# BUCKCONVERTER-MCU.net
KiCad netlist of a schematic drawn in Altium Designer
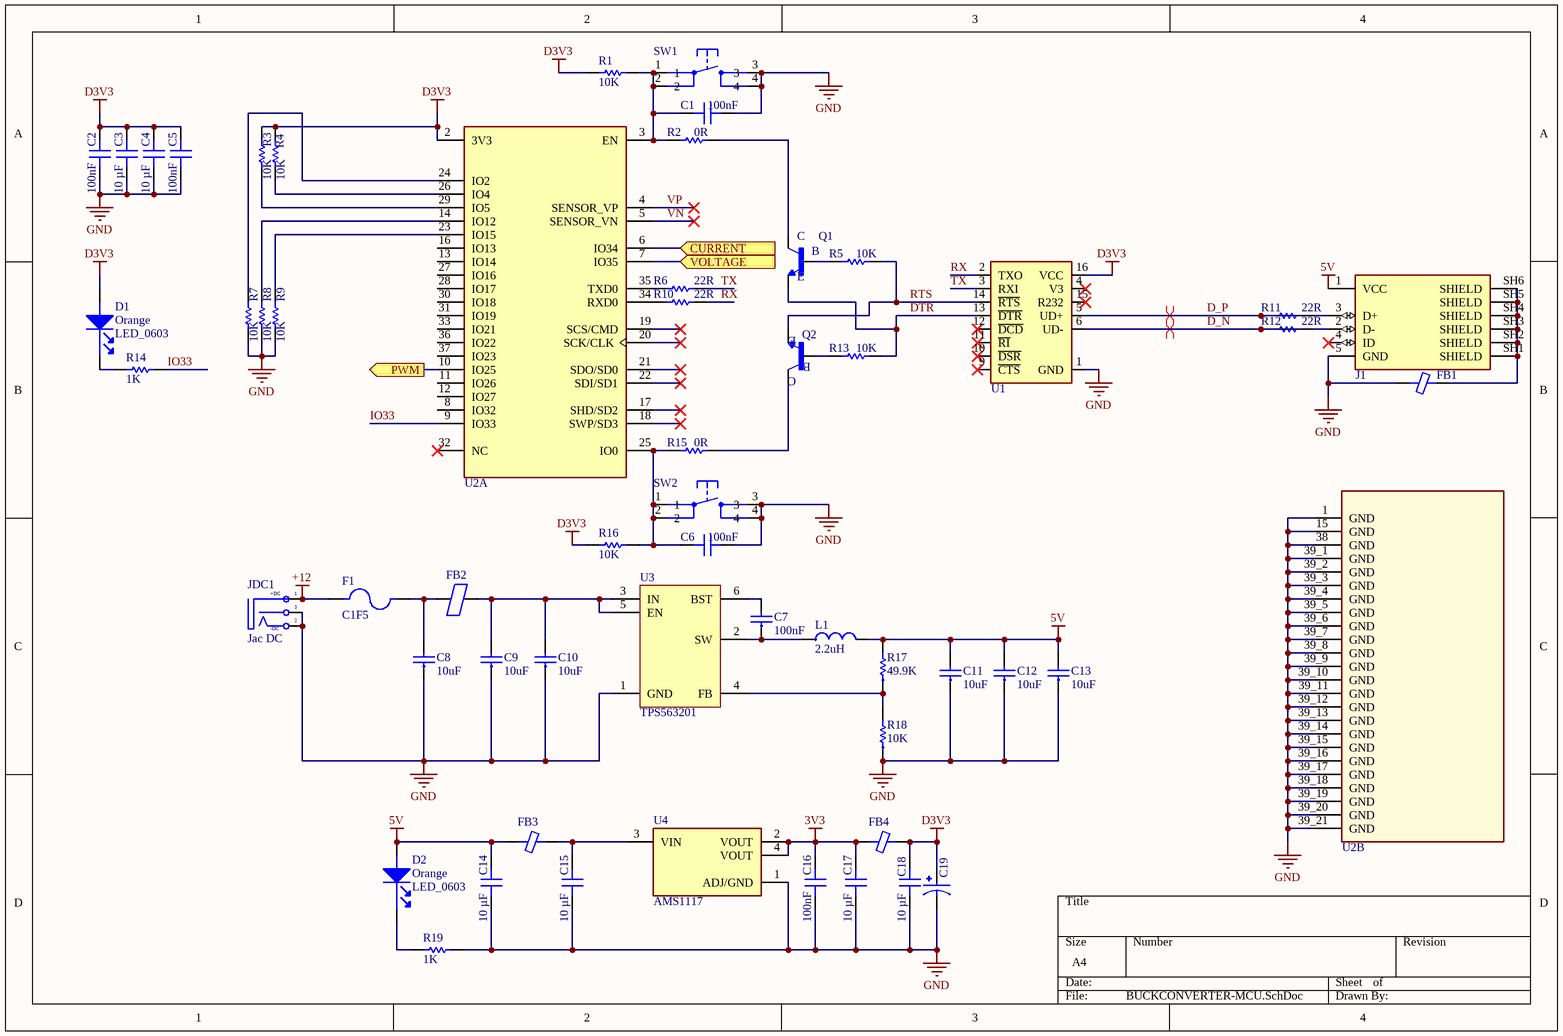
[diagram p0: BUCKCONVERTER-MCU.SchDoc]

(export (version "E")
  (design (tool "Eeschema 10.0.6"))
  (components
    (comp (ref "C1")
      (value "100nF")
      (footprint "CAP 0603")
      (description "CAP0603 X7R 10UF 10% 10V")
      (fields
        (field (name "PART NUMBER") "GMC10X7R106K10NT")
        (field (name "MANUFACTURER") "Cal-Chip Electronics, Inc.")
      )
      (libsource (lib "Celestial Altium Library - altium_library") (part "Capacitor"))
    )
    (comp (ref "C2")
      (value "100nF")
      (footprint "CAP 0603")
      (description "CAP0603 X7R 10UF 10% 10V")
      (fields
        (field (name "PART NUMBER") "GMC10X7R106K10NT")
        (field (name "MANUFACTURER") "Cal-Chip Electronics, Inc.")
      )
      (libsource (lib "Celestial Altium Library - altium_library") (part "Capacitor"))
    )
    (comp (ref "C3")
      (value "10 µF")
      (footprint "CAP 0603")
      (description "CAP0603 X7R 10UF 10% 10V")
      (fields
        (field (name "PART NUMBER") "GMC10X7R106K10NT")
        (field (name "MANUFACTURER") "Cal-Chip Electronics, Inc.")
      )
      (libsource (lib "Celestial Altium Library - altium_library") (part "Capacitor"))
    )
    (comp (ref "C4")
      (value "10 µF")
      (footprint "CAP 0603")
      (description "CAP0603 X7R 10UF 10% 10V")
      (fields
        (field (name "PART NUMBER") "GMC10X7R106K10NT")
        (field (name "MANUFACTURER") "Cal-Chip Electronics, Inc.")
      )
      (libsource (lib "Celestial Altium Library - altium_library") (part "Capacitor"))
    )
    (comp (ref "C5")
      (value "100nF")
      (footprint "CAP 0603")
      (description "CAP0603 X7R 10UF 10% 10V")
      (fields
        (field (name "PART NUMBER") "GMC10X7R106K10NT")
        (field (name "MANUFACTURER") "Cal-Chip Electronics, Inc.")
      )
      (libsource (lib "Celestial Altium Library - altium_library") (part "Capacitor"))
    )
    (comp (ref "C6")
      (value "100nF")
      (footprint "CAP 0603")
      (description "CAP0603 X7R 10UF 10% 10V")
      (fields
        (field (name "PART NUMBER") "GMC10X7R106K10NT")
        (field (name "MANUFACTURER") "Cal-Chip Electronics, Inc.")
      )
      (libsource (lib "Celestial Altium Library - altium_library") (part "Capacitor"))
    )
    (comp (ref "C7")
      (value "100nF")
      (footprint "CAP-CER0603-0.8H")
      (description "CAP CER 100nF 10% 50V X7R 0603 SMD")
      (libsource (lib "2502-GMQLITE-MAIN") (part "CAPCER0001 100nF 10% 50V X7R 0603 SMD_1"))
    )
    (comp (ref "C8")
      (value "10uF")
      (footprint "CAP-CER0402-20mil")
      (description "CAP CER 10uF 20% 6.3V X5R 0402 SMD")
      (libsource (lib "2502-GMQLITE-MAIN") (part "CAPCER0040 10uF 20% 6.3V X5R 0402 SMD"))
    )
    (comp (ref "C9")
      (value "10uF")
      (footprint "CAP-CER0402-20mil")
      (description "CAP CER 10uF 20% 6.3V X5R 0402 SMD")
      (libsource (lib "2502-GMQLITE-MAIN") (part "CAPCER0040 10uF 20% 6.3V X5R 0402 SMD"))
    )
    (comp (ref "C10")
      (value "10uF")
      (footprint "CAP-CER0402-20mil")
      (description "CAP CER 10uF 20% 6.3V X5R 0402 SMD")
      (libsource (lib "2502-GMQLITE-MAIN") (part "CAPCER0040 10uF 20% 6.3V X5R 0402 SMD"))
    )
    (comp (ref "C11")
      (value "10uF")
      (footprint "CAP-CER0402-20mil")
      (description "CAP CER 10uF 20% 6.3V X5R 0402 SMD")
      (libsource (lib "2502-GMQLITE-MAIN") (part "CAPCER0040 10uF 20% 6.3V X5R 0402 SMD"))
    )
    (comp (ref "C12")
      (value "10uF")
      (footprint "CAP-CER0402-20mil")
      (description "CAP CER 10uF 20% 6.3V X5R 0402 SMD")
      (libsource (lib "2502-GMQLITE-MAIN") (part "CAPCER0040 10uF 20% 6.3V X5R 0402 SMD"))
    )
    (comp (ref "C13")
      (value "10uF")
      (footprint "CAP-CER0402-20mil")
      (description "CAP CER 10uF 20% 6.3V X5R 0402 SMD")
      (libsource (lib "2502-GMQLITE-MAIN") (part "CAPCER0040 10uF 20% 6.3V X5R 0402 SMD"))
    )
    (comp (ref "C14")
      (value "10 µF")
      (footprint "CAP 0603")
      (description "CAP0603 X7R 10UF 10% 10V")
      (fields
        (field (name "PART NUMBER") "GMC10X7R106K10NT")
        (field (name "MANUFACTURER") "Cal-Chip Electronics, Inc.")
      )
      (libsource (lib "Celestial Altium Library - altium_library") (part "Capacitor"))
    )
    (comp (ref "C15")
      (value "10 µF")
      (footprint "CAP 0603")
      (description "CAP0603 X7R 10UF 10% 10V")
      (fields
        (field (name "PART NUMBER") "GMC10X7R106K10NT")
        (field (name "MANUFACTURER") "Cal-Chip Electronics, Inc.")
      )
      (libsource (lib "Celestial Altium Library - altium_library") (part "Capacitor"))
    )
    (comp (ref "C16")
      (value "100nF")
      (footprint "CAP 0603")
      (description "CAP0603 X7R 10UF 10% 10V")
      (fields
        (field (name "PART NUMBER") "GMC10X7R106K10NT")
        (field (name "MANUFACTURER") "Cal-Chip Electronics, Inc.")
      )
      (libsource (lib "Celestial Altium Library - altium_library") (part "Capacitor"))
    )
    (comp (ref "C17")
      (value "10 µF")
      (footprint "CAP 0603")
      (description "CAP0603 X7R 10UF 10% 10V")
      (fields
        (field (name "PART NUMBER") "GMC10X7R106K10NT")
        (field (name "MANUFACTURER") "Cal-Chip Electronics, Inc.")
      )
      (libsource (lib "Celestial Altium Library - altium_library") (part "Capacitor"))
    )
    (comp (ref "C18")
      (value "10 µF")
      (footprint "CAP 0603")
      (description "CAP0603 X7R 10UF 10% 10V")
      (fields
        (field (name "PART NUMBER") "GMC10X7R106K10NT")
        (field (name "MANUFACTURER") "Cal-Chip Electronics, Inc.")
      )
      (libsource (lib "Celestial Altium Library - altium_library") (part "Capacitor"))
    )
    (comp (ref "C19")
      (value "ECA1CHG331")
      (footprint "330UF-5mm")
      (fields (field (name "MP") "ECA-1CHG331") (field (name "MF") "Panasonic"))
      (libsource (lib "ECA1CHG331") (part "ECA1CHG331"))
    )
    (comp (ref "D1")
      (value "Orange")
      (footprint "LED")
      (description "LED SMARTLED ORANGE 606NM 0603")
      (fields
        (field (name "MANUFACTURER") "OSRAM Opto Semiconductors Inc")
        (field (name "MANUFACTURER PART NUMBER") "LO L29K-H2K1-24-Z")
        (field (name "PACKAGE / CASE") "LED_0603")
        (field (name "BY") "Hieu.Nguyen_20191030")
      )
      (libsource (lib "Stm32_Flyback_Driver_250814_1") (part "LED ORANGE 606NM 0603"))
    )
    (comp (ref "D2")
      (value "Orange")
      (footprint "LED")
      (description "LED SMARTLED ORANGE 606NM 0603")
      (fields
        (field (name "MANUFACTURER") "OSRAM Opto Semiconductors Inc")
        (field (name "MANUFACTURER PART NUMBER") "LO L29K-H2K1-24-Z")
        (field (name "PACKAGE / CASE") "LED_0603")
        (field (name "BY") "Hieu.Nguyen_20191030")
      )
      (libsource (lib "Stm32_Flyback_Driver_250814_1") (part "LED ORANGE 606NM 0603"))
    )
    (comp (ref "F1")
      (value "C1F5")
      (footprint "FUSE C1F5")
      (description "Fuse Chip Fast Acting 5A 125V SMD Solder Pad 1206 3.2 X 1.58 X 0.63mm")
      (fields (field (name "MANUFACTURER") "Bel TRP"))
      (libsource (lib "POWER_PIN_CAMERA") (part "C1F5"))
    )
    (comp (ref "FB1")
      (value "330 Ohms @ 100 MHz")
      (footprint "FB_0603")
      (description "FERRITE BEAD 330 OHM 0603 1LN")
      (fields
        (field (name "PART NUMBER") "BLM18KG331SH1D")
        (field (name "MANUFACTURER") "Murata Electronics")
      )
      (libsource (lib "Celestial Altium Library - altium_library") (part "Ferrite Chip"))
    )
    (comp (ref "FB2")
      (value "100MHz 2A 50mOhm")
      (footprint "FB 0603")
      (description "Ferrite Beads Multi-Layer 120Ohm 25% 100MHz 2A 50mOhm DCR 0603 Paper T/R")
      (fields
        (field (name "MANUFACTURER") "Murata")
        (field (name "MANUFACTURER PART NUMBER") "BLM18PG121SN1D")
      )
      (libsource (lib "POWER_PIN_CAMERA") (part "BLM18PG121SN1D"))
    )
    (comp (ref "FB3")
      (value "330 Ohms @ 100 MHz")
      (footprint "FB_0603")
      (description "FERRITE BEAD 330 OHM 0603 1LN")
      (fields
        (field (name "PART NUMBER") "BLM18KG331SH1D")
        (field (name "MANUFACTURER") "Murata Electronics")
      )
      (libsource (lib "Celestial Altium Library - altium_library") (part "Ferrite Chip"))
    )
    (comp (ref "FB4")
      (value "330 Ohms @ 100 MHz")
      (footprint "FB_0603")
      (description "FERRITE BEAD 330 OHM 0603 1LN")
      (fields
        (field (name "PART NUMBER") "BLM18KG331SH1D")
        (field (name "MANUFACTURER") "Murata Electronics")
      )
      (libsource (lib "Celestial Altium Library - altium_library") (part "Ferrite Chip"))
    )
    (comp (ref "J1")
      (value "MICRO B")
      (footprint "MICRO USB B")
      (libsource (lib "ESP32-S") (part "MICRO USB B"))
    )
    (comp (ref "JDC1")
      (value "Jac DC")
      (footprint "DC0")
      (description "Jac DC input")
      (libsource (lib "2502-GMQLITE-MAIN") (part "DCIN"))
    )
    (comp (ref "L1")
      (value "2.2uH")
      (footprint "IND-0420-2R2")
      (description "IND MOI 1W2T 2.2uH 20% 5A 0420 SMD")
      (libsource (lib "2502-GMQLITE-MAIN") (part "INDMOI0016 1W2T 2.2uH 20% 5A 0420 SMD"))
    )
    (comp (ref "Q1")
      (value "NMOS")
      (footprint "SOT23-3")
      (description "MMBT3904 Series 40 V CE Breakdown 0.2 A NPN General Purpose Amplifier - SOT-23")
      (fields (field (name "MANUFACTURER") "onsemi") (field (name "MANUFACTURER PART NUMBER") "MMBT3904"))
      (libsource (lib "Stm32_Flyback_Driver_250814_1") (part "MMBT3904"))
    )
    (comp (ref "Q2")
      (value "NMOS")
      (footprint "SOT23-3")
      (description "MMBT3904 Series 40 V CE Breakdown 0.2 A NPN General Purpose Amplifier - SOT-23")
      (fields (field (name "MANUFACTURER") "onsemi") (field (name "MANUFACTURER PART NUMBER") "MMBT3904"))
      (libsource (lib "") (part "MMBT3904_1"))
    )
    (comp (ref "R1")
      (value "10K")
      (footprint "Res 0603")
      (description "Res Thick Film 0603 2.2K Ohm 5% 1/10W ±200ppm/°C Molded SMD SMD Paper T/R")
      (fields
        (field (name "MANUFACTURER") "Vishay")
        (field (name "MANUFACTURER PART NUMBER") "CRCW06032K20JNEA")
      )
      (libsource (lib "Stm32_Flyback_Driver_250814_1") (part "Resistor 2.2K"))
    )
    (comp (ref "R2")
      (value "0R")
      (footprint "Res 0603")
      (description "Res Thick Film 0603 2.2K Ohm 5% 1/10W ±200ppm/°C Molded SMD SMD Paper T/R")
      (fields
        (field (name "MANUFACTURER") "Vishay")
        (field (name "MANUFACTURER PART NUMBER") "CRCW06032K20JNEA")
      )
      (libsource (lib "Stm32_Flyback_Driver_250814_1") (part "Resistor 2.2K"))
    )
    (comp (ref "R3")
      (value "10K")
      (footprint "Res 0603")
      (description "Res Thick Film 0603 2.2K Ohm 5% 1/10W ±200ppm/°C Molded SMD SMD Paper T/R")
      (fields
        (field (name "MANUFACTURER") "Vishay")
        (field (name "MANUFACTURER PART NUMBER") "CRCW06032K20JNEA")
      )
      (libsource (lib "Stm32_Flyback_Driver_250814_1") (part "Resistor 2.2K"))
    )
    (comp (ref "R4")
      (value "10K")
      (footprint "Res 0603")
      (description "Res Thick Film 0603 2.2K Ohm 5% 1/10W ±200ppm/°C Molded SMD SMD Paper T/R")
      (fields
        (field (name "MANUFACTURER") "Vishay")
        (field (name "MANUFACTURER PART NUMBER") "CRCW06032K20JNEA")
      )
      (libsource (lib "Stm32_Flyback_Driver_250814_1") (part "Resistor 2.2K"))
    )
    (comp (ref "R5")
      (value "10K")
      (footprint "Res 0603")
      (description "Res Thick Film 0603 2.2K Ohm 5% 1/10W ±200ppm/°C Molded SMD SMD Paper T/R")
      (fields
        (field (name "MANUFACTURER") "Vishay")
        (field (name "MANUFACTURER PART NUMBER") "CRCW06032K20JNEA")
      )
      (libsource (lib "Stm32_Flyback_Driver_250814_1") (part "Resistor 2.2K"))
    )
    (comp (ref "R6")
      (value "22R")
      (footprint "Res 0603")
      (description "Res Thick Film 0603 2.2K Ohm 5% 1/10W ±200ppm/°C Molded SMD SMD Paper T/R")
      (fields
        (field (name "MANUFACTURER") "Vishay")
        (field (name "MANUFACTURER PART NUMBER") "CRCW06032K20JNEA")
      )
      (libsource (lib "Stm32_Flyback_Driver_250814_1") (part "Resistor 2.2K"))
    )
    (comp (ref "R7")
      (value "10K")
      (footprint "Res 0603")
      (description "Res Thick Film 0603 2.2K Ohm 5% 1/10W ±200ppm/°C Molded SMD SMD Paper T/R")
      (fields
        (field (name "MANUFACTURER") "Vishay")
        (field (name "MANUFACTURER PART NUMBER") "CRCW06032K20JNEA")
      )
      (libsource (lib "Stm32_Flyback_Driver_250814_1") (part "Resistor 2.2K"))
    )
    (comp (ref "R8")
      (value "10K")
      (footprint "Res 0603")
      (description "Res Thick Film 0603 2.2K Ohm 5% 1/10W ±200ppm/°C Molded SMD SMD Paper T/R")
      (fields
        (field (name "MANUFACTURER") "Vishay")
        (field (name "MANUFACTURER PART NUMBER") "CRCW06032K20JNEA")
      )
      (libsource (lib "Stm32_Flyback_Driver_250814_1") (part "Resistor 2.2K"))
    )
    (comp (ref "R9")
      (value "10K")
      (footprint "Res 0603")
      (description "Res Thick Film 0603 2.2K Ohm 5% 1/10W ±200ppm/°C Molded SMD SMD Paper T/R")
      (fields
        (field (name "MANUFACTURER") "Vishay")
        (field (name "MANUFACTURER PART NUMBER") "CRCW06032K20JNEA")
      )
      (libsource (lib "Stm32_Flyback_Driver_250814_1") (part "Resistor 2.2K"))
    )
    (comp (ref "R10")
      (value "22R")
      (footprint "Res 0603")
      (description "Res Thick Film 0603 2.2K Ohm 5% 1/10W ±200ppm/°C Molded SMD SMD Paper T/R")
      (fields
        (field (name "MANUFACTURER") "Vishay")
        (field (name "MANUFACTURER PART NUMBER") "CRCW06032K20JNEA")
      )
      (libsource (lib "Stm32_Flyback_Driver_250814_1") (part "Resistor 2.2K"))
    )
    (comp (ref "R11")
      (value "22R")
      (footprint "Res 0603")
      (description "Res Thick Film 0603 2.2K Ohm 5% 1/10W ±200ppm/°C Molded SMD SMD Paper T/R")
      (fields
        (field (name "MANUFACTURER") "Vishay")
        (field (name "MANUFACTURER PART NUMBER") "CRCW06032K20JNEA")
      )
      (libsource (lib "Stm32_Flyback_Driver_250814_1") (part "Resistor 2.2K"))
    )
    (comp (ref "R12")
      (value "22R")
      (footprint "Res 0603")
      (description "Res Thick Film 0603 2.2K Ohm 5% 1/10W ±200ppm/°C Molded SMD SMD Paper T/R")
      (fields
        (field (name "MANUFACTURER") "Vishay")
        (field (name "MANUFACTURER PART NUMBER") "CRCW06032K20JNEA")
      )
      (libsource (lib "Stm32_Flyback_Driver_250814_1") (part "Resistor 2.2K"))
    )
    (comp (ref "R13")
      (value "10K")
      (footprint "Res 0603")
      (description "Res Thick Film 0603 2.2K Ohm 5% 1/10W ±200ppm/°C Molded SMD SMD Paper T/R")
      (fields
        (field (name "MANUFACTURER") "Vishay")
        (field (name "MANUFACTURER PART NUMBER") "CRCW06032K20JNEA")
      )
      (libsource (lib "Stm32_Flyback_Driver_250814_1") (part "Resistor 2.2K"))
    )
    (comp (ref "R14")
      (value "1K")
      (footprint "Res 0603")
      (description "Res Thick Film 0603 2.2K Ohm 5% 1/10W ±200ppm/°C Molded SMD SMD Paper T/R")
      (fields
        (field (name "MANUFACTURER") "Vishay")
        (field (name "MANUFACTURER PART NUMBER") "CRCW06032K20JNEA")
      )
      (libsource (lib "Stm32_Flyback_Driver_250814_1") (part "Resistor 2.2K"))
    )
    (comp (ref "R15")
      (value "0R")
      (footprint "Res 0603")
      (description "Res Thick Film 0603 2.2K Ohm 5% 1/10W ±200ppm/°C Molded SMD SMD Paper T/R")
      (fields
        (field (name "MANUFACTURER") "Vishay")
        (field (name "MANUFACTURER PART NUMBER") "CRCW06032K20JNEA")
      )
      (libsource (lib "Stm32_Flyback_Driver_250814_1") (part "Resistor 2.2K"))
    )
    (comp (ref "R16")
      (value "10K")
      (footprint "Res 0603")
      (description "Res Thick Film 0603 2.2K Ohm 5% 1/10W ±200ppm/°C Molded SMD SMD Paper T/R")
      (fields
        (field (name "MANUFACTURER") "Vishay")
        (field (name "MANUFACTURER PART NUMBER") "CRCW06032K20JNEA")
      )
      (libsource (lib "Stm32_Flyback_Driver_250814_1") (part "Resistor 2.2K"))
    )
    (comp (ref "R17")
      (value "49.9K")
      (footprint "RES-CHP0603-0.45H-272")
      (description "RES CHP 2K7 1% 1/10W 0603 SMD")
      (libsource (lib "2502-GMQLITE-MAIN") (part "RESCHP0195 2K7 1% 0603 SMD"))
    )
    (comp (ref "R18")
      (value "10K")
      (footprint "RES-CHP0603-0.45H-272")
      (description "RES CHP 2K7 1% 1/10W 0603 SMD")
      (libsource (lib "2502-GMQLITE-MAIN") (part "RESCHP0195 2K7 1% 0603 SMD"))
    )
    (comp (ref "R19")
      (value "1K")
      (footprint "Res 0603")
      (description "Res Thick Film 0603 2.2K Ohm 5% 1/10W ±200ppm/°C Molded SMD SMD Paper T/R")
      (fields
        (field (name "MANUFACTURER") "Vishay")
        (field (name "MANUFACTURER PART NUMBER") "CRCW06032K20JNEA")
      )
      (libsource (lib "Stm32_Flyback_Driver_250814_1") (part "Resistor 2.2K"))
    )
    (comp (ref "SW1")
      (value "SW2")
      (footprint "SWITCH")
      (description "Switch button 4 pin")
      (libsource (lib "Stm32_Flyback_Driver_250814_1") (part "SW2"))
    )
    (comp (ref "SW2")
      (value "SW2")
      (footprint "SWITCH")
      (description "Switch button 4 pin")
      (libsource (lib "Stm32_Flyback_Driver_250814_1") (part "SW2"))
    )
    (comp (ref "U1") (value "CH340C") (footprint "CH340C") (libsource (lib "ESP32-S") (part "CH340C")))
    (comp (ref "U2")
      (value "ESP32-WROOM-32UE-N8")
      (footprint "ESP32S")
      (description "Multiprotocol Modules SMD module ESP32-WROOM-32UE, ESP32-D0WD-V3, ESP32 ECO V3,")
      (fields (field (name "MANUFACTURER") "Espressif Systems"))
      (libsource (lib "ESP32-S") (part "ESP32-WROOM-32UE-N8"))
    )
    (comp (ref "U3")
      (value "TPS563201")
      (footprint "SOT23-6")
      (description "ICS OCV BCK TPS563201 3A SOT23-6 SMD")
      (libsource (lib "2502-GMQLITE-MAIN") (part "ICSOCV0021 BCK TPS563201 3A SOT23-6 SMD"))
    )
    (comp (ref "U4")
      (value "AMS1117")
      (footprint "AMS1117")
      (description "1A LOW DROPOUT VOLTAGE REGULATOR SOT-223")
      (fields (field (name "MF") "Advanced Monolithic Systems"))
      (libsource (lib "AMS1117") (part "AMS1117"))
    )
  )
  (nets
    (net (code "1") (name "+12") (class "Default")
      (node (ref "F1") (pin "1") (pinfunction "1_1") (pintype "passive"))
      (node (ref "JDC1") (pin "1") (pinfunction "T_1") (pintype "passive"))
    )
    (net (code "2") (name "/CURRENT") (class "Default")
      (node (ref "U2") (pin "6") (pinfunction "IO34_6") (pintype "passive"))
    )
    (net (code "3") (name "/DTR") (class "Default")
      (node (ref "Q1") (pin "2") (pinfunction "E_2") (pintype "passive"))
      (node (ref "R13") (pin "2") (pinfunction "2_2") (pintype "passive"))
      (node (ref "U1") (pin "13") (pinfunction "~{DTR}_13") (pintype "passive"))
    )
    (net (code "4") (name "/D_N") (class "Default")
      (node (ref "R12") (pin "1") (pinfunction "1_1") (pintype "passive"))
      (node (ref "U1") (pin "6") (pinfunction "UD-_6") (pintype "passive"))
    )
    (net (code "5") (name "/D_P") (class "Default")
      (node (ref "R11") (pin "1") (pinfunction "1_1") (pintype "passive"))
      (node (ref "U1") (pin "5") (pinfunction "UD+_5") (pintype "passive"))
    )
    (net (code "6") (name "/IO33") (class "Default")
      (node (ref "R14") (pin "2") (pinfunction "2_2") (pintype "passive"))
      (node (ref "U2") (pin "9") (pinfunction "IO33_9") (pintype "passive"))
    )
    (net (code "7") (name "/PWM") (class "Default")
      (node (ref "U2") (pin "10") (pinfunction "IO25_10") (pintype "passive"))
    )
    (net (code "8") (name "/RTS") (class "Default")
      (node (ref "Q2") (pin "2") (pinfunction "E_2") (pintype "passive"))
      (node (ref "R5") (pin "2") (pinfunction "2_2") (pintype "passive"))
      (node (ref "U1") (pin "14") (pinfunction "~{RTS}_14") (pintype "passive"))
    )
    (net (code "9") (name "/RX") (class "Default")
      (node (ref "R10") (pin "2") (pinfunction "2_2") (pintype "passive"))
      (node (ref "U1") (pin "2") (pinfunction "TXO_2") (pintype "passive"))
    )
    (net (code "10") (name "/TX") (class "Default")
      (node (ref "R6") (pin "2") (pinfunction "2_2") (pintype "passive"))
      (node (ref "U1") (pin "3") (pinfunction "RXI_3") (pintype "passive"))
    )
    (net (code "11") (name "/VN") (class "Default")
      (node (ref "U2") (pin "5") (pinfunction "SENSOR_VN_5") (pintype "passive+no_connect"))
    )
    (net (code "12") (name "/VOLTAGE") (class "Default")
      (node (ref "U2") (pin "7") (pinfunction "IO35_7") (pintype "passive"))
    )
    (net (code "13") (name "/VP") (class "Default")
      (node (ref "U2") (pin "4") (pinfunction "SENSOR_VP_4") (pintype "passive+no_connect"))
    )
    (net (code "14") (name "3V3") (class "Default")
      (node (ref "C16") (pin "2") (pinfunction "2_2") (pintype "passive"))
      (node (ref "C17") (pin "2") (pinfunction "2_2") (pintype "passive"))
      (node (ref "FB4") (pin "1") (pinfunction "1_1") (pintype "passive"))
      (node (ref "U4") (pin "2") (pinfunction "VOUT_2") (pintype "passive"))
      (node (ref "U4") (pin "4") (pinfunction "VOUT_4") (pintype "passive"))
    )
    (net (code "15") (name "5V") (class "Default")
      (node (ref "C11") (pin "2") (pinfunction "2_2") (pintype "passive"))
      (node (ref "C12") (pin "2") (pinfunction "2_2") (pintype "passive"))
      (node (ref "C13") (pin "2") (pinfunction "2_2") (pintype "passive"))
      (node (ref "C14") (pin "2") (pinfunction "2_2") (pintype "passive"))
      (node (ref "D2") (pin "1") (pinfunction "ANODE_1") (pintype "passive"))
      (node (ref "FB3") (pin "1") (pinfunction "1_1") (pintype "passive"))
      (node (ref "J1") (pin "1") (pinfunction "VCC_1") (pintype "power_in"))
      (node (ref "L1") (pin "2") (pinfunction "2_2") (pintype "passive"))
      (node (ref "R17") (pin "2") (pinfunction "2_2") (pintype "passive"))
    )
    (net (code "16") (name "D3V3") (class "Default")
      (node (ref "C18") (pin "2") (pinfunction "2_2") (pintype "passive"))
      (node (ref "C19") (pin "1") (pinfunction "1_1") (pintype "passive"))
      (node (ref "C2") (pin "2") (pinfunction "2_2") (pintype "passive"))
      (node (ref "C3") (pin "2") (pinfunction "2_2") (pintype "passive"))
      (node (ref "C4") (pin "2") (pinfunction "2_2") (pintype "passive"))
      (node (ref "C5") (pin "2") (pinfunction "2_2") (pintype "passive"))
      (node (ref "D1") (pin "1") (pinfunction "ANODE_1") (pintype "passive"))
      (node (ref "FB4") (pin "2") (pinfunction "2_2") (pintype "passive"))
      (node (ref "R1") (pin "1") (pinfunction "1_1") (pintype "passive"))
      (node (ref "R16") (pin "1") (pinfunction "1_1") (pintype "passive"))
      (node (ref "R3") (pin "2") (pinfunction "2_2") (pintype "passive"))
      (node (ref "R4") (pin "2") (pinfunction "2_2") (pintype "passive"))
      (node (ref "U1") (pin "16") (pinfunction "VCC_16") (pintype "passive"))
      (node (ref "U2") (pin "2") (pinfunction "3V3_2") (pintype "passive"))
    )
    (net (code "17") (name "GND") (class "Default")
      (node (ref "C1") (pin "1") (pinfunction "1_1") (pintype "passive"))
      (node (ref "C10") (pin "1") (pinfunction "1_1") (pintype "passive"))
      (node (ref "C11") (pin "1") (pinfunction "1_1") (pintype "passive"))
      (node (ref "C12") (pin "1") (pinfunction "1_1") (pintype "passive"))
      (node (ref "C13") (pin "1") (pinfunction "1_1") (pintype "passive"))
      (node (ref "C14") (pin "1") (pinfunction "1_1") (pintype "passive"))
      (node (ref "C15") (pin "1") (pinfunction "1_1") (pintype "passive"))
      (node (ref "C16") (pin "1") (pinfunction "1_1") (pintype "passive"))
      (node (ref "C17") (pin "1") (pinfunction "1_1") (pintype "passive"))
      (node (ref "C18") (pin "1") (pinfunction "1_1") (pintype "passive"))
      (node (ref "C19") (pin "2") (pinfunction "2_2") (pintype "passive"))
      (node (ref "C2") (pin "1") (pinfunction "1_1") (pintype "passive"))
      (node (ref "C3") (pin "1") (pinfunction "1_1") (pintype "passive"))
      (node (ref "C4") (pin "1") (pinfunction "1_1") (pintype "passive"))
      (node (ref "C5") (pin "1") (pinfunction "1_1") (pintype "passive"))
      (node (ref "C6") (pin "1") (pinfunction "1_1") (pintype "passive"))
      (node (ref "C8") (pin "1") (pinfunction "1_1") (pintype "passive"))
      (node (ref "C9") (pin "1") (pinfunction "1_1") (pintype "passive"))
      (node (ref "FB1") (pin "1") (pinfunction "1_1") (pintype "passive"))
      (node (ref "J1") (pin "5") (pinfunction "GND_5") (pintype "power_in"))
      (node (ref "JDC1") (pin "2") (pinfunction "TN_2") (pintype "passive"))
      (node (ref "JDC1") (pin "3") (pinfunction "S_3") (pintype "power_in"))
      (node (ref "R18") (pin "1") (pinfunction "1_1") (pintype "passive"))
      (node (ref "R19") (pin "2") (pinfunction "2_2") (pintype "passive"))
      (node (ref "R7") (pin "1") (pinfunction "1_1") (pintype "passive"))
      (node (ref "R8") (pin "1") (pinfunction "1_1") (pintype "passive"))
      (node (ref "R9") (pin "1") (pinfunction "1_1") (pintype "passive"))
      (node (ref "SW1") (pin "3") (pinfunction "3_3") (pintype "passive"))
      (node (ref "SW1") (pin "4") (pinfunction "4_4") (pintype "passive"))
      (node (ref "SW2") (pin "3") (pinfunction "3_3") (pintype "passive"))
      (node (ref "SW2") (pin "4") (pinfunction "4_4") (pintype "passive"))
      (node (ref "U1") (pin "1") (pinfunction "GND_1") (pintype "passive"))
      (node (ref "U2") (pin "1") (pinfunction "GND_1") (pintype "passive"))
      (node (ref "U2") (pin "15") (pinfunction "GND_15") (pintype "passive"))
      (node (ref "U2") (pin "38") (pinfunction "GND_38") (pintype "passive"))
      (node (ref "U2") (pin "39_1") (pinfunction "GND_39_1") (pintype "passive"))
      (node (ref "U2") (pin "39_10") (pinfunction "GND_39_10") (pintype "passive"))
      (node (ref "U2") (pin "39_11") (pinfunction "GND_39_11") (pintype "passive"))
      (node (ref "U2") (pin "39_12") (pinfunction "GND_39_12") (pintype "passive"))
      (node (ref "U2") (pin "39_13") (pinfunction "GND_39_13") (pintype "passive"))
      (node (ref "U2") (pin "39_14") (pinfunction "GND_39_14") (pintype "passive"))
      (node (ref "U2") (pin "39_15") (pinfunction "GND_39_15") (pintype "passive"))
      (node (ref "U2") (pin "39_16") (pinfunction "GND_39_16") (pintype "passive"))
      (node (ref "U2") (pin "39_17") (pinfunction "GND_39_17") (pintype "passive"))
      (node (ref "U2") (pin "39_18") (pinfunction "GND_39_18") (pintype "passive"))
      (node (ref "U2") (pin "39_19") (pinfunction "GND_39_19") (pintype "passive"))
      (node (ref "U2") (pin "39_2") (pinfunction "GND_39_2") (pintype "passive"))
      (node (ref "U2") (pin "39_20") (pinfunction "GND_39_20") (pintype "passive"))
      (node (ref "U2") (pin "39_21") (pinfunction "GND_39_21") (pintype "passive"))
      (node (ref "U2") (pin "39_3") (pinfunction "GND_39_3") (pintype "passive"))
      (node (ref "U2") (pin "39_4") (pinfunction "GND_39_4") (pintype "passive"))
      (node (ref "U2") (pin "39_5") (pinfunction "GND_39_5") (pintype "passive"))
      (node (ref "U2") (pin "39_6") (pinfunction "GND_39_6") (pintype "passive"))
      (node (ref "U2") (pin "39_7") (pinfunction "GND_39_7") (pintype "passive"))
      (node (ref "U2") (pin "39_8") (pinfunction "GND_39_8") (pintype "passive"))
      (node (ref "U2") (pin "39_9") (pinfunction "GND_39_9") (pintype "passive"))
      (node (ref "U3") (pin "1") (pinfunction "GND_1") (pintype "power_in"))
      (node (ref "U4") (pin "1") (pinfunction "ADJ/GND_1") (pintype "power_in"))
    )
    (net (code "18") (name "Net-(C8-Pad2)") (class "Default")
      (node (ref "C8") (pin "2") (pinfunction "2_2") (pintype "passive"))
      (node (ref "F1") (pin "2") (pinfunction "2_2") (pintype "passive"))
      (node (ref "FB2") (pin "1") (pinfunction "1_1") (pintype "passive"))
    )
    (net (code "19") (name "Net-(D1-cathode)") (class "Default")
      (node (ref "D1") (pin "2") (pinfunction "cathode_2") (pintype "passive"))
      (node (ref "R14") (pin "1") (pinfunction "1_1") (pintype "passive"))
    )
    (net (code "20") (name "Net-(D2-cathode)") (class "Default")
      (node (ref "D2") (pin "2") (pinfunction "cathode_2") (pintype "passive"))
      (node (ref "R19") (pin "1") (pinfunction "1_1") (pintype "passive"))
    )
    (net (code "21") (name "Net-(FB1-Pad2)") (class "Default")
      (node (ref "FB1") (pin "2") (pinfunction "2_2") (pintype "passive"))
      (node (ref "J1") (pin "SH1") (pinfunction "SHIELD_SH1") (pintype "passive"))
      (node (ref "J1") (pin "SH2") (pinfunction "SHIELD_SH2") (pintype "passive"))
      (node (ref "J1") (pin "SH3") (pinfunction "SHIELD_SH3") (pintype "passive"))
      (node (ref "J1") (pin "SH4") (pinfunction "SHIELD_SH4") (pintype "passive"))
      (node (ref "J1") (pin "SH5") (pinfunction "SHIELD_SH5") (pintype "passive"))
      (node (ref "J1") (pin "SH6") (pinfunction "SHIELD_SH6") (pintype "passive"))
    )
    (net (code "22") (name "Net-(J1-D+)") (class "Default")
      (node (ref "J1") (pin "3") (pinfunction "D+_3") (pintype "bidirectional"))
      (node (ref "R11") (pin "2") (pinfunction "2_2") (pintype "passive"))
    )
    (net (code "23") (name "Net-(J1-D-)") (class "Default")
      (node (ref "J1") (pin "2") (pinfunction "D-_2") (pintype "bidirectional"))
      (node (ref "R12") (pin "2") (pinfunction "2_2") (pintype "passive"))
    )
    (net (code "24") (name "Net-(Q1-B)") (class "Default")
      (node (ref "Q1") (pin "1") (pinfunction "B_1") (pintype "passive"))
      (node (ref "R5") (pin "1") (pinfunction "1_1") (pintype "passive"))
    )
    (net (code "25") (name "Net-(Q1-C)") (class "Default")
      (node (ref "Q1") (pin "3") (pinfunction "C_3") (pintype "passive"))
      (node (ref "R2") (pin "2") (pinfunction "2_2") (pintype "passive"))
    )
    (net (code "26") (name "Net-(Q2-B)") (class "Default")
      (node (ref "Q2") (pin "1") (pinfunction "B_1") (pintype "passive"))
      (node (ref "R13") (pin "1") (pinfunction "1_1") (pintype "passive"))
    )
    (net (code "27") (name "Net-(Q2-C)") (class "Default")
      (node (ref "Q2") (pin "3") (pinfunction "C_3") (pintype "passive"))
      (node (ref "R15") (pin "2") (pinfunction "2_2") (pintype "passive"))
    )
    (net (code "28") (name "Net-(U2A-EN)") (class "Default")
      (node (ref "C1") (pin "2") (pinfunction "2_2") (pintype "passive"))
      (node (ref "R1") (pin "2") (pinfunction "2_2") (pintype "passive"))
      (node (ref "R2") (pin "1") (pinfunction "1_1") (pintype "passive"))
      (node (ref "SW1") (pin "1") (pinfunction "1_1") (pintype "passive"))
      (node (ref "SW1") (pin "2") (pinfunction "2_2") (pintype "passive"))
      (node (ref "U2") (pin "3") (pinfunction "EN_3") (pintype "passive"))
    )
    (net (code "29") (name "Net-(U2A-IO0)") (class "Default")
      (node (ref "C6") (pin "2") (pinfunction "2_2") (pintype "passive"))
      (node (ref "R15") (pin "1") (pinfunction "1_1") (pintype "passive"))
      (node (ref "R16") (pin "2") (pinfunction "2_2") (pintype "passive"))
      (node (ref "SW2") (pin "1") (pinfunction "1_1") (pintype "passive"))
      (node (ref "SW2") (pin "2") (pinfunction "2_2") (pintype "passive"))
      (node (ref "U2") (pin "25") (pinfunction "IO0_25") (pintype "passive"))
    )
    (net (code "30") (name "Net-(U2A-IO2)") (class "Default")
      (node (ref "R7") (pin "2") (pinfunction "2_2") (pintype "passive"))
      (node (ref "U2") (pin "24") (pinfunction "IO2_24") (pintype "passive"))
    )
    (net (code "31") (name "Net-(U2A-IO4)") (class "Default")
      (node (ref "R4") (pin "1") (pinfunction "1_1") (pintype "passive"))
      (node (ref "U2") (pin "26") (pinfunction "IO4_26") (pintype "passive"))
    )
    (net (code "32") (name "Net-(U2A-IO5)") (class "Default")
      (node (ref "R3") (pin "1") (pinfunction "1_1") (pintype "passive"))
      (node (ref "U2") (pin "29") (pinfunction "IO5_29") (pintype "passive"))
    )
    (net (code "33") (name "Net-(U2A-IO12)") (class "Default")
      (node (ref "R8") (pin "2") (pinfunction "2_2") (pintype "passive"))
      (node (ref "U2") (pin "14") (pinfunction "IO12_14") (pintype "passive"))
    )
    (net (code "34") (name "Net-(U2A-IO15)") (class "Default")
      (node (ref "R9") (pin "2") (pinfunction "2_2") (pintype "passive"))
      (node (ref "U2") (pin "23") (pinfunction "IO15_23") (pintype "passive"))
    )
    (net (code "35") (name "Net-(U2A-RXD0)") (class "Default")
      (node (ref "R10") (pin "1") (pinfunction "1_1") (pintype "passive"))
      (node (ref "U2") (pin "34") (pinfunction "RXD0_34") (pintype "passive"))
    )
    (net (code "36") (name "Net-(U2A-TXD0)") (class "Default")
      (node (ref "R6") (pin "1") (pinfunction "1_1") (pintype "passive"))
      (node (ref "U2") (pin "35") (pinfunction "TXD0_35") (pintype "passive"))
    )
    (net (code "37") (name "Net-(U3-BST)") (class "Default")
      (node (ref "C7") (pin "2") (pinfunction "2_2") (pintype "passive"))
      (node (ref "U3") (pin "6") (pinfunction "BST_6") (pintype "passive"))
    )
    (net (code "38") (name "Net-(U3-EN)") (class "Default")
      (node (ref "C10") (pin "2") (pinfunction "2_2") (pintype "passive"))
      (node (ref "C9") (pin "2") (pinfunction "2_2") (pintype "passive"))
      (node (ref "FB2") (pin "2") (pinfunction "2_2") (pintype "passive"))
      (node (ref "U3") (pin "3") (pinfunction "IN_3") (pintype "power_in"))
      (node (ref "U3") (pin "5") (pinfunction "EN_5") (pintype "passive"))
    )
    (net (code "39") (name "Net-(U3-FB)") (class "Default")
      (node (ref "R17") (pin "1") (pinfunction "1_1") (pintype "passive"))
      (node (ref "R18") (pin "2") (pinfunction "2_2") (pintype "passive"))
      (node (ref "U3") (pin "4") (pinfunction "FB_4") (pintype "passive"))
    )
    (net (code "40") (name "Net-(U3-SW)") (class "Default")
      (node (ref "C7") (pin "1") (pinfunction "1_1") (pintype "passive"))
      (node (ref "L1") (pin "1") (pinfunction "1_1") (pintype "passive"))
      (node (ref "U3") (pin "2") (pinfunction "SW_2") (pintype "passive"))
    )
    (net (code "41") (name "Net-(U4-VIN)") (class "Default")
      (node (ref "C15") (pin "2") (pinfunction "2_2") (pintype "passive"))
      (node (ref "FB3") (pin "2") (pinfunction "2_2") (pintype "passive"))
      (node (ref "U4") (pin "3") (pinfunction "VIN_3") (pintype "passive"))
    )
    (net (code "42") (name "unconnected-(J1-ID-Pad4)") (class "Default")
      (node (ref "J1") (pin "4") (pinfunction "ID_4") (pintype "bidirectional+no_connect"))
    )
    (net (code "43") (name "unconnected-(U1-R232-Pad15)") (class "Default")
      (node (ref "U1") (pin "15") (pinfunction "R232_15") (pintype "passive+no_connect"))
    )
    (net (code "44") (name "unconnected-(U1-V3-Pad4)") (class "Default")
      (node (ref "U1") (pin "4") (pinfunction "V3_4") (pintype "passive+no_connect"))
    )
    (net (code "45") (name "unconnected-(U1-~{CTS}-Pad9)") (class "Default")
      (node (ref "U1") (pin "9") (pinfunction "~{CTS}_9") (pintype "passive+no_connect"))
    )
    (net (code "46") (name "unconnected-(U1-~{DCD}-Pad12)") (class "Default")
      (node (ref "U1") (pin "12") (pinfunction "~{DCD}_12") (pintype "passive+no_connect"))
    )
    (net (code "47") (name "unconnected-(U1-~{DSR}-Pad10)") (class "Default")
      (node (ref "U1") (pin "10") (pinfunction "~{DSR}_10") (pintype "passive+no_connect"))
    )
    (net (code "48") (name "unconnected-(U1-~{RI}-Pad11)") (class "Default")
      (node (ref "U1") (pin "11") (pinfunction "~{RI}_11") (pintype "passive+no_connect"))
    )
    (net (code "49") (name "unconnected-(U2A-IO13-Pad16)") (class "Default")
      (node (ref "U2") (pin "16") (pinfunction "IO13_16") (pintype "passive"))
    )
    (net (code "50") (name "unconnected-(U2A-IO14-Pad13)") (class "Default")
      (node (ref "U2") (pin "13") (pinfunction "IO14_13") (pintype "passive"))
    )
    (net (code "51") (name "unconnected-(U2A-IO16-Pad27)") (class "Default")
      (node (ref "U2") (pin "27") (pinfunction "IO16_27") (pintype "passive"))
    )
    (net (code "52") (name "unconnected-(U2A-IO17-Pad28)") (class "Default")
      (node (ref "U2") (pin "28") (pinfunction "IO17_28") (pintype "passive"))
    )
    (net (code "53") (name "unconnected-(U2A-IO18-Pad30)") (class "Default")
      (node (ref "U2") (pin "30") (pinfunction "IO18_30") (pintype "passive"))
    )
    (net (code "54") (name "unconnected-(U2A-IO19-Pad31)") (class "Default")
      (node (ref "U2") (pin "31") (pinfunction "IO19_31") (pintype "passive"))
    )
    (net (code "55") (name "unconnected-(U2A-IO21-Pad33)") (class "Default")
      (node (ref "U2") (pin "33") (pinfunction "IO21_33") (pintype "passive"))
    )
    (net (code "56") (name "unconnected-(U2A-IO22-Pad36)") (class "Default")
      (node (ref "U2") (pin "36") (pinfunction "IO22_36") (pintype "passive"))
    )
    (net (code "57") (name "unconnected-(U2A-IO23-Pad37)") (class "Default")
      (node (ref "U2") (pin "37") (pinfunction "IO23_37") (pintype "passive"))
    )
    (net (code "58") (name "unconnected-(U2A-IO26-Pad11)") (class "Default")
      (node (ref "U2") (pin "11") (pinfunction "IO26_11") (pintype "passive"))
    )
    (net (code "59") (name "unconnected-(U2A-IO27-Pad12)") (class "Default")
      (node (ref "U2") (pin "12") (pinfunction "IO27_12") (pintype "passive"))
    )
    (net (code "60") (name "unconnected-(U2A-IO32-Pad8)") (class "Default")
      (node (ref "U2") (pin "8") (pinfunction "IO32_8") (pintype "passive"))
    )
    (net (code "61") (name "unconnected-(U2A-NC-Pad32)") (class "Default")
      (node (ref "U2") (pin "32") (pinfunction "NC_32") (pintype "passive+no_connect"))
    )
    (net (code "62") (name "unconnected-(U2A-SCK{slash}CLK-Pad20)") (class "Default")
      (node (ref "U2") (pin "20") (pinfunction "SCK/CLK_20") (pintype "passive+no_connect"))
    )
    (net (code "63") (name "unconnected-(U2A-SCS{slash}CMD-Pad19)") (class "Default")
      (node (ref "U2") (pin "19") (pinfunction "SCS/CMD_19") (pintype "passive+no_connect"))
    )
    (net (code "64") (name "unconnected-(U2A-SDI{slash}SD1-Pad22)") (class "Default")
      (node (ref "U2") (pin "22") (pinfunction "SDI/SD1_22") (pintype "passive+no_connect"))
    )
    (net (code "65") (name "unconnected-(U2A-SDO{slash}SD0-Pad21)") (class "Default")
      (node (ref "U2") (pin "21") (pinfunction "SDO/SD0_21") (pintype "passive+no_connect"))
    )
    (net (code "66") (name "unconnected-(U2A-SHD{slash}SD2-Pad17)") (class "Default")
      (node (ref "U2") (pin "17") (pinfunction "SHD/SD2_17") (pintype "passive+no_connect"))
    )
    (net (code "67") (name "unconnected-(U2A-SWP{slash}SD3-Pad18)") (class "Default")
      (node (ref "U2") (pin "18") (pinfunction "SWP/SD3_18") (pintype "passive+no_connect"))
    )
  )
)
